# SPWM_PS_V1_00.net
KiCad netlist of a schematic drawn in Altium Designer
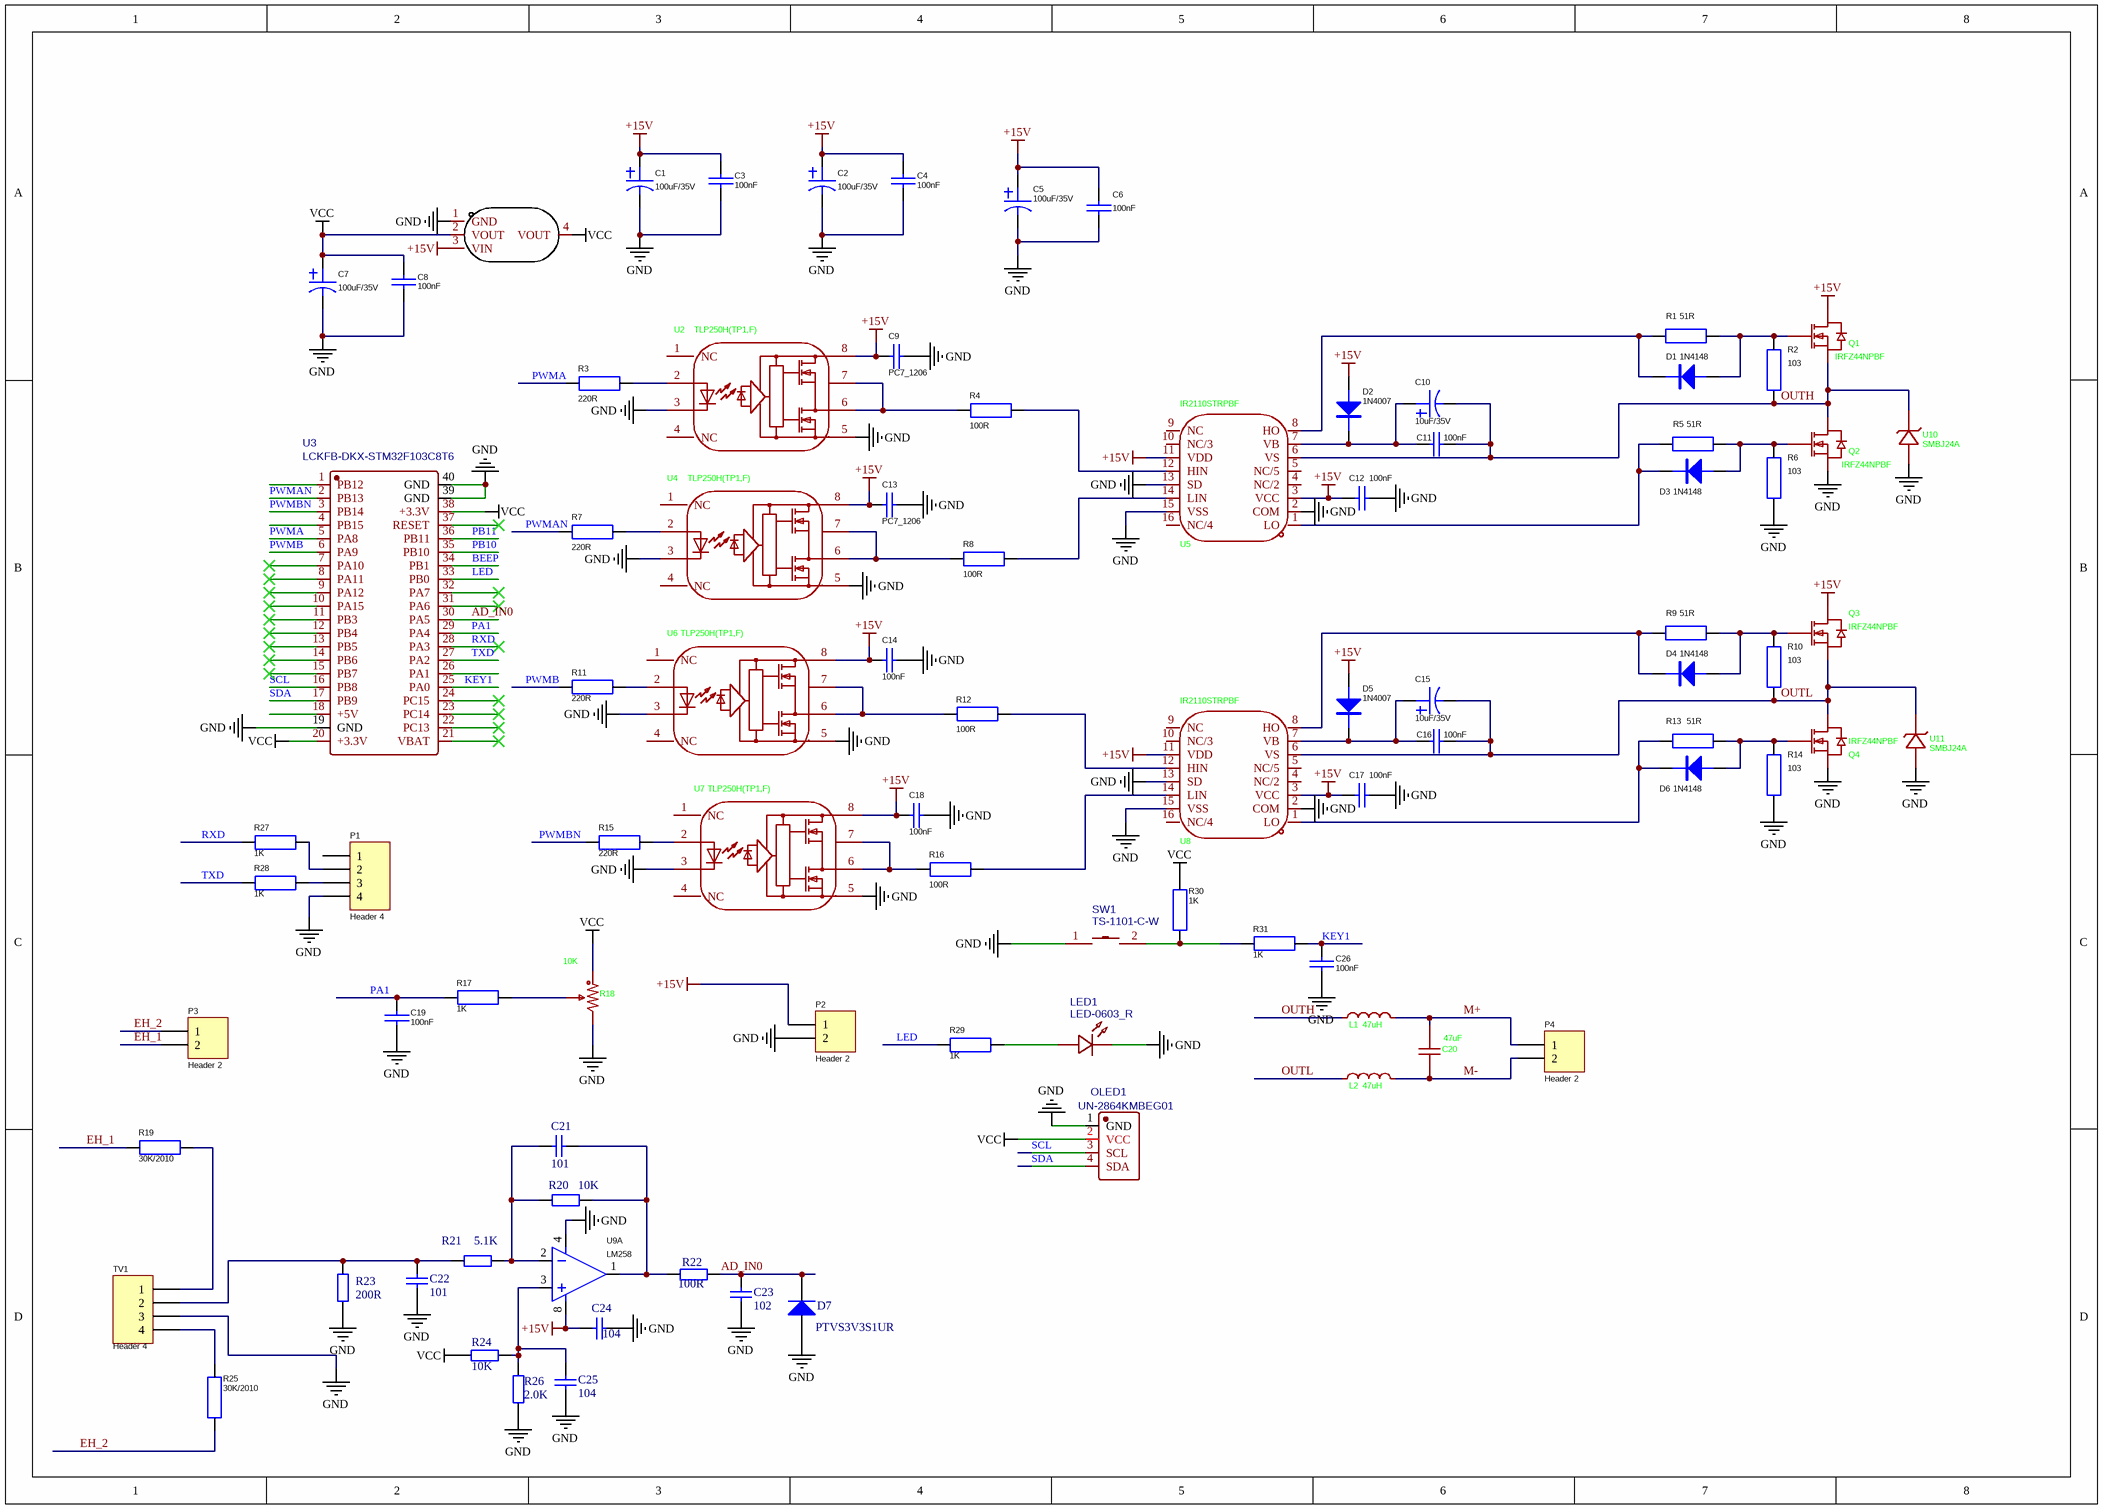
[diagram p0: SPWM_PS_V1.00.SCHDOC]

(export (version "E")
  (design (tool "Eeschema 10.0.6"))
  (components
    (comp (ref "C1")
      (value "100uF/35V")
      (footprint "PCD-10135-MB-36_100UF/35V")
      (description "PCD-10135-MB-36")
      (libsource (lib "Schlib") (part "PCD_100uF/35V"))
    )
    (comp (ref "C2")
      (value "100uF/35V")
      (footprint "PCD-10135-MB-36_100UF/35V")
      (description "PCD-10135-MB-36")
      (libsource (lib "Schlib") (part "PCD_100uF/35V"))
    )
    (comp (ref "C3")
      (value "100nF")
      (footprint "PC7-*****-KN-0A_0805")
      (description "PC7-*****-KM-0A_1206")
      (libsource (lib "Schlib") (part "PC7_1206"))
    )
    (comp (ref "C4")
      (value "100nF")
      (footprint "PC7-*****-KN-0A_0805")
      (description "PC7-*****-KM-0A_1206")
      (libsource (lib "Schlib") (part "PC7_1206"))
    )
    (comp (ref "C5")
      (value "100uF/35V")
      (footprint "PCD-10135-MB-36_100UF/35V")
      (description "PCD-10135-MB-36")
      (libsource (lib "Schlib") (part "PCD_100uF/35V"))
    )
    (comp (ref "C6")
      (value "100nF")
      (footprint "PC7-*****-KN-0A_0805")
      (description "PC7-*****-KM-0A_1206")
      (libsource (lib "Schlib") (part "PC7_1206"))
    )
    (comp (ref "C7")
      (value "100uF/35V")
      (footprint "PCD-10135-MB-36_100UF/35V")
      (description "PCD-10135-MB-36")
      (libsource (lib "Schlib") (part "PCD_100uF/35V"))
    )
    (comp (ref "C8")
      (value "100nF")
      (footprint "PC7-*****-KN-0A_0805")
      (description "PC7-*****-KM-0A_1206")
      (libsource (lib "Schlib") (part "PC7_1206"))
    )
    (comp (ref "C9")
      (value "PC7_1206")
      (footprint "PC7-*****-KN-0A_0805")
      (description "PC7-*****-KM-0A_1206")
      (libsource (lib "Schlib") (part "PC7_1206"))
    )
    (comp (ref "C10")
      (value "10uF/35V")
      (footprint "PCD-10050-MA-26_10UF/50V")
      (description "PCD-10135-MB-36")
      (libsource (lib "Schlib") (part "PCD_100uF/35V"))
    )
    (comp (ref "C11")
      (value "100nF")
      (footprint "PC7-*****-KN-0A_0805")
      (description "PC7-*****-KM-0A_1206")
      (libsource (lib "Schlib") (part "PC7_1206"))
    )
    (comp (ref "C12")
      (value "100nF")
      (footprint "PC7-*****-KN-0A_0805")
      (description "PC7-*****-KM-0A_1206")
      (libsource (lib "Schlib") (part "PC7_1206"))
    )
    (comp (ref "C13")
      (value "PC7_1206")
      (footprint "PC7-*****-KN-0A_0805")
      (description "PC7-*****-KM-0A_1206")
      (libsource (lib "Schlib") (part "PC7_1206"))
    )
    (comp (ref "C14")
      (value "100nF")
      (footprint "PC7-*****-KN-0A_0805")
      (description "PC7-*****-KM-0A_1206")
      (libsource (lib "Schlib") (part "PC7_1206"))
    )
    (comp (ref "C15")
      (value "10uF/35V")
      (footprint "PCD-10050-MA-26_10UF/50V")
      (description "PCD-10135-MB-36")
      (libsource (lib "Schlib") (part "PCD_100uF/35V"))
    )
    (comp (ref "C16")
      (value "100nF")
      (footprint "PC7-*****-KN-0A_0805")
      (description "PC7-*****-KM-0A_1206")
      (libsource (lib "Schlib") (part "PC7_1206"))
    )
    (comp (ref "C17")
      (value "100nF")
      (footprint "PC7-*****-KN-0A_0805")
      (description "PC7-*****-KM-0A_1206")
      (libsource (lib "Schlib") (part "PC7_1206"))
    )
    (comp (ref "C18")
      (value "100nF")
      (footprint "PC7-*****-KN-0A_0805")
      (description "PC7-*****-KM-0A_1206")
      (libsource (lib "Schlib") (part "PC7_1206"))
    )
    (comp (ref "C19")
      (value "100nF")
      (footprint "PC7-*****-KN-0A_0805")
      (description "PC7-*****-KM-0A_1206")
      (libsource (lib "Schlib") (part "PC7_1206"))
    )
    (comp (ref "C20")
      (value "47uF")
      (footprint "C2220")
      (fields (field (name "MANUFACTURER PART") "FS55X226K101LRG"))
      (libsource (lib "altium-import") (part "root_1_FS55X226K101LRG_"))
    )
    (comp (ref "C21")
      (value "101")
      (footprint "PC7-*****-KN-0A_0805")
      (description "Capacitor (Semiconductor SIM Model)")
      (fields (field (name "PUBLISHER") "Altium Limited"))
      (libsource (lib "Miscellaneous Devices") (part "Cap Semi"))
    )
    (comp (ref "C22")
      (value "101")
      (footprint "PC7-*****-KN-0A_0805")
      (description "Capacitor (Semiconductor SIM Model)")
      (fields (field (name "PUBLISHER") "Altium Limited"))
      (libsource (lib "Miscellaneous Devices") (part "Cap Semi"))
    )
    (comp (ref "C23")
      (value "102")
      (footprint "PC7-*****-KN-0A_0805")
      (description "Capacitor (Semiconductor SIM Model)")
      (fields (field (name "PUBLISHER") "Altium Limited"))
      (libsource (lib "Miscellaneous Devices") (part "Cap Semi"))
    )
    (comp (ref "C24")
      (value "104")
      (footprint "PC7-*****-KN-0A_0805")
      (description "Capacitor (Semiconductor SIM Model)")
      (fields (field (name "PUBLISHER") "Altium Limited"))
      (libsource (lib "Miscellaneous Devices") (part "Cap Semi"))
    )
    (comp (ref "C25")
      (value "104")
      (footprint "PC7-*****-KN-0A_0805")
      (description "Capacitor (Semiconductor SIM Model)")
      (fields (field (name "PUBLISHER") "Altium Limited"))
      (libsource (lib "Miscellaneous Devices") (part "Cap Semi"))
    )
    (comp (ref "C26")
      (value "100nF")
      (footprint "PC7-*****-KN-0A_0805")
      (description "PC7-*****-KM-0A_1206")
      (libsource (lib "Schlib") (part "PC7_1206"))
    )
    (comp (ref "D1")
      (value "1N4148")
      (footprint "PDD-00020-30-2A_RLS4148NTE-11-K")
      (description "PDD-00020-30-2A")
      (libsource (lib "Schlib") (part "PDD_RLS4148NTE-11-K"))
    )
    (comp (ref "D2")
      (value "1N4007")
      (footprint "PDD-00020-30-2A_RLS4148NTE-11-K")
      (description "PDD-00020-30-2A")
      (libsource (lib "Schlib") (part "PDD_RLS4148NTE-11-K"))
    )
    (comp (ref "D3")
      (value "1N4148")
      (footprint "PDD-00020-30-2A_RLS4148NTE-11-K")
      (description "PDD-00020-30-2A")
      (libsource (lib "Schlib") (part "PDD_RLS4148NTE-11-K"))
    )
    (comp (ref "D4")
      (value "1N4148")
      (footprint "PDD-00020-30-2A_RLS4148NTE-11-K")
      (description "PDD-00020-30-2A")
      (libsource (lib "Schlib") (part "PDD_RLS4148NTE-11-K"))
    )
    (comp (ref "D5")
      (value "1N4007")
      (footprint "PDD-00020-30-2A_RLS4148NTE-11-K")
      (description "PDD-00020-30-2A")
      (libsource (lib "Schlib") (part "PDD_RLS4148NTE-11-K"))
    )
    (comp (ref "D6")
      (value "1N4148")
      (footprint "PDD-00020-30-2A_RLS4148NTE-11-K")
      (description "PDD-00020-30-2A")
      (libsource (lib "Schlib") (part "PDD_RLS4148NTE-11-K"))
    )
    (comp (ref "D7")
      (value "PTVS3V3S1UR")
      (footprint "SOD123")
      (description "Default Diode")
      (fields (field (name "PUBLISHER") "Altium Limited"))
      (libsource (lib "Miscellaneous Devices") (part "Diode"))
    )
    (comp (ref "L1")
      (value "47uH")
      (footprint "IND-SMD_L13.8-W12.6_H6.5")
      (fields (field (name "MANUFACTURER PART") "YSPI1365-470M"))
      (libsource (lib "altium-import") (part "root_0_YSPI1365-470M_"))
    )
    (comp (ref "L2")
      (value "47uH")
      (footprint "IND-SMD_L13.8-W12.6_H6.5")
      (fields (field (name "MANUFACTURER PART") "YSPI1365-470M"))
      (libsource (lib "altium-import") (part "root_0_YSPI1365-470M_"))
    )
    (comp (ref "LED1")
      (value "LED-0603_R")
      (footprint "LED0603_RED")
      (fields
        (field (name "MANUFACTURER PART") "19-217/R6C-AL1M2VY/3T")
        (field (name "CONTRIBUTOR") "LCEDA_01")
      )
      (libsource (lib "altium-import") (part "root_0_LED-0603_R_"))
    )
    (comp (ref "OLED1")
      (value "UN-2864KMBEG01")
      (footprint "OLED-TH_4P-P2.54-L27.8-W27.3")
      (fields (field (name "CONTRIBUTOR") "lcsc"))
      (libsource (lib "altium-import") (part "root_0_UN-2864KMBEG01_"))
    )
    (comp (ref "P1")
      (value "Header 4")
      (footprint "HDR1X4")
      (description "Header, 4-Pin")
      (fields (field (name "PUBLISHER") "Altium Limited"))
      (libsource (lib "") (part "Header 4_1"))
    )
    (comp (ref "P2")
      (value "Header 2")
      (footprint "CONN-TH_2P-P5.00_WJ128V-5.0-2P")
      (description "Header, 2-Pin")
      (fields (field (name "PUBLISHER") "Altium Limited"))
      (libsource (lib "Miscellaneous Connectors") (part "Header 2"))
    )
    (comp (ref "P3")
      (value "Header 2")
      (footprint "CONN-TH_2P-P5.00_WJ128V-5.0-2P")
      (description "Header, 2-Pin")
      (fields (field (name "PUBLISHER") "Altium Limited"))
      (libsource (lib "Miscellaneous Connectors") (part "Header 2"))
    )
    (comp (ref "P4")
      (value "Header 2")
      (footprint "CONN-TH_2P-P5.00_WJ128V-5.0-2P")
      (description "Header, 2-Pin")
      (fields (field (name "PUBLISHER") "Altium Limited"))
      (libsource (lib "Miscellaneous Connectors") (part "Header 2"))
    )
    (comp (ref "Q1")
      (value "IRFZ44NPBF")
      (footprint "TO-220-3_L10.0-W4.5-P2.54-L")
      (libsource (lib "altium-import") (part "root_0_IRFZ44NPBF_"))
    )
    (comp (ref "Q2")
      (value "IRFZ44NPBF")
      (footprint "TO-220-3_L10.0-W4.5-P2.54-L")
      (libsource (lib "altium-import") (part "root_0_IRFZ44NPBF_"))
    )
    (comp (ref "Q3")
      (value "IRFZ44NPBF")
      (footprint "TO-220-3_L10.0-W4.5-P2.54-L")
      (libsource (lib "altium-import") (part "root_0_IRFZ44NPBF_"))
    )
    (comp (ref "Q4")
      (value "IRFZ44NPBF")
      (footprint "TO-220-3_L10.0-W4.5-P2.54-L")
      (libsource (lib "altium-import") (part "root_0_IRFZ44NPBF_"))
    )
    (comp (ref "R1")
      (value "51R")
      (footprint "PRC-*****-1M-0A_0805")
      (description "PRC-*****-2M-0A_1206")
      (libsource (lib "Schlib") (part "PRC_1206"))
    )
    (comp (ref "R2")
      (value "103")
      (footprint "PRC-*****-1M-0A_0805")
      (description "PRC-*****-2M-0A_1206")
      (libsource (lib "Schlib") (part "PRC_1206"))
    )
    (comp (ref "R3")
      (value "220R")
      (footprint "PRC-*****-1M-0A_0805")
      (description "PRC-*****-2M-0A_1206")
      (libsource (lib "Schlib") (part "PRC_1206"))
    )
    (comp (ref "R4")
      (value "100R")
      (footprint "PRC-*****-1M-0A_0805")
      (description "PRC-*****-2M-0A_1206")
      (libsource (lib "Schlib") (part "PRC_1206"))
    )
    (comp (ref "R5")
      (value "51R")
      (footprint "PRC-*****-1M-0A_0805")
      (description "PRC-*****-2M-0A_1206")
      (libsource (lib "Schlib") (part "PRC_1206"))
    )
    (comp (ref "R6")
      (value "103")
      (footprint "PRC-*****-1M-0A_0805")
      (description "PRC-*****-2M-0A_1206")
      (libsource (lib "Schlib") (part "PRC_1206"))
    )
    (comp (ref "R7")
      (value "220R")
      (footprint "PRC-*****-1M-0A_0805")
      (description "PRC-*****-2M-0A_1206")
      (libsource (lib "Schlib") (part "PRC_1206"))
    )
    (comp (ref "R8")
      (value "100R")
      (footprint "PRC-*****-1M-0A_0805")
      (description "PRC-*****-2M-0A_1206")
      (libsource (lib "Schlib") (part "PRC_1206"))
    )
    (comp (ref "R9")
      (value "51R")
      (footprint "PRC-*****-1M-0A_0805")
      (description "PRC-*****-2M-0A_1206")
      (libsource (lib "Schlib") (part "PRC_1206"))
    )
    (comp (ref "R10")
      (value "103")
      (footprint "PRC-*****-1M-0A_0805")
      (description "PRC-*****-2M-0A_1206")
      (libsource (lib "Schlib") (part "PRC_1206"))
    )
    (comp (ref "R11")
      (value "220R")
      (footprint "PRC-*****-1M-0A_0805")
      (description "PRC-*****-2M-0A_1206")
      (libsource (lib "Schlib") (part "PRC_1206"))
    )
    (comp (ref "R12")
      (value "100R")
      (footprint "PRC-*****-1M-0A_0805")
      (description "PRC-*****-2M-0A_1206")
      (libsource (lib "Schlib") (part "PRC_1206"))
    )
    (comp (ref "R13")
      (value "51R")
      (footprint "PRC-*****-1M-0A_0805")
      (description "PRC-*****-2M-0A_1206")
      (libsource (lib "Schlib") (part "PRC_1206"))
    )
    (comp (ref "R14")
      (value "103")
      (footprint "PRC-*****-1M-0A_0805")
      (description "PRC-*****-2M-0A_1206")
      (libsource (lib "Schlib") (part "PRC_1206"))
    )
    (comp (ref "R15")
      (value "220R")
      (footprint "PRC-*****-1M-0A_0805")
      (description "PRC-*****-2M-0A_1206")
      (libsource (lib "Schlib") (part "PRC_1206"))
    )
    (comp (ref "R16")
      (value "100R")
      (footprint "PRC-*****-1M-0A_0805")
      (description "PRC-*****-2M-0A_1206")
      (libsource (lib "Schlib") (part "PRC_1206"))
    )
    (comp (ref "R17")
      (value "1K")
      (footprint "PRC-*****-1M-0A_0805")
      (description "PRC-*****-2M-0A_1206")
      (libsource (lib "Schlib") (part "PRC_1206"))
    )
    (comp (ref "R18")
      (value "10K")
      (footprint "RES-ADJ-TH_RK09Y11L0001")
      (fields (field (name "MANUFACTURER PART") "RK09Y11L0001"))
      (libsource (lib "altium-import") (part "root_1_RK09Y11L0001_"))
    )
    (comp (ref "R19")
      (value "30K/2010")
      (footprint "PRC-*****-CM-0A_2010")
      (description "PRC-*****-CM-0A_2010")
      (libsource (lib "Schlib") (part "PRC_2010"))
    )
    (comp (ref "R20") (value "10K") (footprint "PRM-*****-1N-0A_0805") (libsource (lib "*") (part "RES-SM")))
    (comp (ref "R21") (value "5.1K") (footprint "PRM-*****-1N-0A_0805") (libsource (lib "*") (part "RES-SM")))
    (comp (ref "R22") (value "100R") (footprint "PRM-*****-1N-0A_0805") (libsource (lib "*") (part "RES-SM")))
    (comp (ref "R23")
      (value "200R")
      (footprint "PRM-*****-1N-0A_0805")
      (libsource (lib "") (part "RES-SM_3"))
    )
    (comp (ref "R24") (value "10K") (footprint "PRM-*****-1N-0A_0805") (libsource (lib "") (part "RES-SM_1")))
    (comp (ref "R25")
      (value "30K/2010")
      (footprint "PRC-*****-CM-0A_2010")
      (description "PRC-*****-CM-0A_2010")
      (libsource (lib "Schlib") (part "PRC_2010"))
    )
    (comp (ref "R26")
      (value "2.0K")
      (footprint "PRM-*****-1N-0A_0805")
      (libsource (lib "") (part "RES-SM_2"))
    )
    (comp (ref "R27")
      (value "1K")
      (footprint "PRC-*****-1M-0A_0805")
      (description "PRC-*****-2M-0A_1206")
      (libsource (lib "Schlib") (part "PRC_1206"))
    )
    (comp (ref "R28")
      (value "1K")
      (footprint "PRC-*****-1M-0A_0805")
      (description "PRC-*****-2M-0A_1206")
      (libsource (lib "Schlib") (part "PRC_1206"))
    )
    (comp (ref "R29")
      (value "1K")
      (footprint "PRC-*****-1M-0A_0805")
      (description "PRC-*****-2M-0A_1206")
      (libsource (lib "Schlib") (part "PRC_1206"))
    )
    (comp (ref "R30")
      (value "1K")
      (footprint "PRC-*****-1M-0A_0805")
      (description "PRC-*****-2M-0A_1206")
      (libsource (lib "Schlib") (part "PRC_1206"))
    )
    (comp (ref "R31")
      (value "1K")
      (footprint "PRC-*****-1M-0A_0805")
      (description "PRC-*****-2M-0A_1206")
      (libsource (lib "Schlib") (part "PRC_1206"))
    )
    (comp (ref "SW1")
      (value "TS-1101-C-W")
      (footprint "SW-SMD_L6.0-W3.3-LS8.0")
      (fields (field (name "CONTRIBUTOR") "LCSC"))
      (libsource (lib "altium-import") (part "root_0_TS-1101-C-W_"))
    )
    (comp (ref "TV1")
      (value "Header 4")
      (footprint "TV0815-1")
      (description "Header, 4-Pin")
      (fields (field (name "PUBLISHER") "Altium Limited"))
      (libsource (lib "Miscellaneous Connectors") (part "Header 4"))
    )
    (comp (ref "U1")
      (value "AMS1117-3.3")
      (footprint "SOT-223-3_L6.5-W3.4-P2.30-LS7.0-BR")
      (fields (field (name "MANUFACTURER") "AMS"))
      (libsource (lib "iomod_V1.00_20240818_1") (part "AMS1117-3.3_C6186"))
    )
    (comp (ref "U2")
      (value "TLP250H(TP1,F)")
      (footprint "SMD-8_L9.6-W6.4-P2.54-LS9.6-BL")
      (libsource (lib "altium-import") (part "root_0_TLP250H(TP1,F)_"))
    )
    (comp (ref "U3")
      (value "LCKFB-DKX-STM32F103C8T6")
      (footprint "CONN-TH_L53.3-W22.9_STM32F103C8T6-CARD")
      (fields (field (name "CONTRIBUTOR") "lcsc"))
      (libsource (lib "altium-import") (part "root_0_LCKFB-DKX-STM32F103C8T6_"))
    )
    (comp (ref "U4")
      (value "TLP250H(TP1,F)")
      (footprint "SMD-8_L9.6-W6.4-P2.54-LS9.6-BL")
      (libsource (lib "altium-import") (part "root_0_TLP250H(TP1,F)_"))
    )
    (comp (ref "U5")
      (value "IR2110STRPBF")
      (footprint "SOIC-16_L10.3-W7.5-P1.27-LS10.3-BL")
      (libsource (lib "altium-import") (part "root_2_IR2110STRPBF_"))
    )
    (comp (ref "U6")
      (value "TLP250H(TP1,F)")
      (footprint "SMD-8_L9.6-W6.4-P2.54-LS9.6-BL")
      (libsource (lib "altium-import") (part "root_0_TLP250H(TP1,F)_"))
    )
    (comp (ref "U7")
      (value "TLP250H(TP1,F)")
      (footprint "SMD-8_L9.6-W6.4-P2.54-LS9.6-BL")
      (libsource (lib "altium-import") (part "root_0_TLP250H(TP1,F)_"))
    )
    (comp (ref "U8")
      (value "IR2110STRPBF")
      (footprint "SOIC-16_L10.3-W7.5-P1.27-LS10.3-BL")
      (libsource (lib "altium-import") (part "root_2_IR2110STRPBF_"))
    )
    (comp (ref "U9")
      (value "LM258")
      (footprint "LM358-SOIC-8")
      (description "PIC-01330-01-20")
      (libsource (lib "Schlib") (part "PIC_NJM2904"))
    )
    (comp (ref "U10")
      (value "SMBJ24A")
      (footprint "SMB_L4.3-W3.6-LS5.3-RD")
      (libsource (lib "altium-import") (part "root_3_SMBJ24A_C19077578_"))
    )
    (comp (ref "U11")
      (value "SMBJ24A")
      (footprint "SMB_L4.3-W3.6-LS5.3-RD")
      (libsource (lib "altium-import") (part "root_3_SMBJ24A_C19077578_"))
    )
  )
  (nets
    (net (code "1") (name "+15V") (class "Default")
      (node (ref "C1") (pin "1") (pinfunction "1_1") (pintype "passive"))
      (node (ref "C12") (pin "1") (pinfunction "1_1") (pintype "passive"))
      (node (ref "C13") (pin "1") (pinfunction "1_1") (pintype "passive"))
      (node (ref "C14") (pin "1") (pinfunction "1_1") (pintype "passive"))
      (node (ref "C17") (pin "1") (pinfunction "1_1") (pintype "passive"))
      (node (ref "C18") (pin "1") (pinfunction "1_1") (pintype "passive"))
      (node (ref "C2") (pin "1") (pinfunction "1_1") (pintype "passive"))
      (node (ref "C24") (pin "1") (pinfunction "1_1") (pintype "passive"))
      (node (ref "C3") (pin "1") (pinfunction "1_1") (pintype "passive"))
      (node (ref "C4") (pin "1") (pinfunction "1_1") (pintype "passive"))
      (node (ref "C5") (pin "1") (pinfunction "1_1") (pintype "passive"))
      (node (ref "C6") (pin "1") (pinfunction "1_1") (pintype "passive"))
      (node (ref "C9") (pin "1") (pinfunction "1_1") (pintype "passive"))
      (node (ref "D2") (pin "2") (pinfunction "2_2") (pintype "passive"))
      (node (ref "D5") (pin "2") (pinfunction "2_2") (pintype "passive"))
      (node (ref "P2") (pin "1") (pinfunction "1_1") (pintype "passive"))
      (node (ref "Q1") (pin "2") (pinfunction "D_2") (pintype "passive"))
      (node (ref "Q3") (pin "2") (pinfunction "D_2") (pintype "passive"))
      (node (ref "U1") (pin "3") (pinfunction "VIN_3") (pintype "passive"))
      (node (ref "U2") (pin "8") (pinfunction "VCC_8") (pintype "passive"))
      (node (ref "U4") (pin "8") (pinfunction "VCC_8") (pintype "passive"))
      (node (ref "U5") (pin "11") (pinfunction "VDD_11") (pintype "passive"))
      (node (ref "U5") (pin "3") (pinfunction "VCC_3") (pintype "passive"))
      (node (ref "U6") (pin "8") (pinfunction "VCC_8") (pintype "passive"))
      (node (ref "U7") (pin "8") (pinfunction "VCC_8") (pintype "passive"))
      (node (ref "U8") (pin "11") (pinfunction "VDD_11") (pintype "passive"))
      (node (ref "U8") (pin "3") (pinfunction "VCC_3") (pintype "passive"))
      (node (ref "U9") (pin "8") (pintype "passive"))
    )
    (net (code "2") (name "/AD_IN0") (class "Default")
      (node (ref "C23") (pin "1") (pinfunction "1_1") (pintype "passive"))
      (node (ref "D7") (pin "2") (pinfunction "K_2") (pintype "passive"))
      (node (ref "R22") (pin "1") (pinfunction "1_1") (pintype "passive"))
      (node (ref "U3") (pin "30") (pinfunction "PA5_30") (pintype "passive"))
    )
    (net (code "3") (name "/BEEP") (class "Default")
      (node (ref "U3") (pin "34") (pinfunction "PB1_34") (pintype "passive"))
    )
    (net (code "4") (name "/EH_1") (class "Default")
      (node (ref "P3") (pin "2") (pinfunction "2_2") (pintype "passive"))
      (node (ref "R19") (pin "2") (pinfunction "2_2") (pintype "passive"))
    )
    (net (code "5") (name "/EH_2") (class "Default")
      (node (ref "P3") (pin "1") (pinfunction "1_1") (pintype "passive"))
      (node (ref "R25") (pin "1") (pinfunction "1_1") (pintype "passive"))
    )
    (net (code "6") (name "/KEY1") (class "Default")
      (node (ref "C26") (pin "2") (pinfunction "2_2") (pintype "passive"))
      (node (ref "R31") (pin "2") (pinfunction "2_2") (pintype "passive"))
      (node (ref "U3") (pin "25") (pinfunction "PA0_25") (pintype "passive"))
    )
    (net (code "7") (name "/LED") (class "Default")
      (node (ref "R29") (pin "1") (pinfunction "1_1") (pintype "passive"))
      (node (ref "U3") (pin "33") (pinfunction "PB0_33") (pintype "passive"))
    )
    (net (code "8") (name "/M+") (class "Default")
      (node (ref "C20") (pin "2") (pinfunction "2_2") (pintype "passive"))
      (node (ref "L1") (pin "2") (pinfunction "2_2") (pintype "passive"))
      (node (ref "P4") (pin "1") (pinfunction "1_1") (pintype "passive"))
    )
    (net (code "9") (name "/M-") (class "Default")
      (node (ref "C20") (pin "1") (pinfunction "1_1") (pintype "passive"))
      (node (ref "L2") (pin "2") (pinfunction "2_2") (pintype "passive"))
      (node (ref "P4") (pin "2") (pinfunction "2_2") (pintype "passive"))
    )
    (net (code "10") (name "/OUTH") (class "Default")
      (node (ref "C10") (pin "2") (pinfunction "2_2") (pintype "passive"))
      (node (ref "C11") (pin "2") (pinfunction "2_2") (pintype "passive"))
      (node (ref "L1") (pin "1") (pinfunction "1_1") (pintype "passive"))
      (node (ref "Q1") (pin "3") (pinfunction "S_3") (pintype "passive"))
      (node (ref "Q2") (pin "2") (pinfunction "D_2") (pintype "passive"))
      (node (ref "R2") (pin "1") (pinfunction "1_1") (pintype "passive"))
      (node (ref "U10") (pin "1") (pinfunction "C_1") (pintype "passive"))
      (node (ref "U5") (pin "6") (pinfunction "VS_6") (pintype "passive"))
    )
    (net (code "11") (name "/OUTL") (class "Default")
      (node (ref "C15") (pin "2") (pinfunction "2_2") (pintype "passive"))
      (node (ref "C16") (pin "2") (pinfunction "2_2") (pintype "passive"))
      (node (ref "L2") (pin "1") (pinfunction "1_1") (pintype "passive"))
      (node (ref "Q3") (pin "3") (pinfunction "S_3") (pintype "passive"))
      (node (ref "Q4") (pin "2") (pinfunction "D_2") (pintype "passive"))
      (node (ref "R10") (pin "1") (pinfunction "1_1") (pintype "passive"))
      (node (ref "U11") (pin "1") (pinfunction "C_1") (pintype "passive"))
      (node (ref "U8") (pin "6") (pinfunction "VS_6") (pintype "passive"))
    )
    (net (code "12") (name "/PA1") (class "Default")
      (node (ref "C19") (pin "2") (pinfunction "2_2") (pintype "passive"))
      (node (ref "R17") (pin "1") (pinfunction "1_1") (pintype "passive"))
      (node (ref "U3") (pin "29") (pinfunction "PA4_29") (pintype "passive"))
    )
    (net (code "13") (name "/PB10") (class "Default")
      (node (ref "U3") (pin "35") (pinfunction "PB10_35") (pintype "passive"))
    )
    (net (code "14") (name "/PB11") (class "Default")
      (node (ref "U3") (pin "36") (pinfunction "PB11_36") (pintype "passive"))
    )
    (net (code "15") (name "/PWMA") (class "Default")
      (node (ref "R3") (pin "1") (pinfunction "1_1") (pintype "passive"))
      (node (ref "U3") (pin "5") (pinfunction "PA8_5") (pintype "passive"))
    )
    (net (code "16") (name "/PWMAN") (class "Default")
      (node (ref "R7") (pin "1") (pinfunction "1_1") (pintype "passive"))
      (node (ref "U3") (pin "2") (pinfunction "PB13_2") (pintype "passive"))
    )
    (net (code "17") (name "/PWMB") (class "Default")
      (node (ref "R11") (pin "1") (pinfunction "1_1") (pintype "passive"))
      (node (ref "U3") (pin "6") (pinfunction "PA9_6") (pintype "passive"))
    )
    (net (code "18") (name "/PWMBN") (class "Default")
      (node (ref "R15") (pin "1") (pinfunction "1_1") (pintype "passive"))
      (node (ref "U3") (pin "3") (pinfunction "PB14_3") (pintype "passive"))
    )
    (net (code "19") (name "/RXD") (class "Default")
      (node (ref "R27") (pin "1") (pinfunction "1_1") (pintype "passive"))
      (node (ref "U3") (pin "28") (pinfunction "PA3_28") (pintype "passive"))
    )
    (net (code "20") (name "/SCL") (class "Default")
      (node (ref "OLED1") (pin "3") (pinfunction "SCL_3") (pintype "passive"))
      (node (ref "U3") (pin "16") (pinfunction "PB8_16") (pintype "passive"))
    )
    (net (code "21") (name "/SDA") (class "Default")
      (node (ref "OLED1") (pin "4") (pinfunction "SDA_4") (pintype "passive"))
      (node (ref "U3") (pin "17") (pinfunction "PB9_17") (pintype "passive"))
    )
    (net (code "22") (name "/TXD") (class "Default")
      (node (ref "R28") (pin "1") (pinfunction "1_1") (pintype "passive"))
      (node (ref "U3") (pin "27") (pinfunction "PA2_27") (pintype "passive"))
    )
    (net (code "23") (name "GND") (class "Default")
      (node (ref "C1") (pin "2") (pinfunction "2_2") (pintype "passive"))
      (node (ref "C12") (pin "2") (pinfunction "2_2") (pintype "passive"))
      (node (ref "C13") (pin "2") (pinfunction "2_2") (pintype "passive"))
      (node (ref "C14") (pin "2") (pinfunction "2_2") (pintype "passive"))
      (node (ref "C17") (pin "2") (pinfunction "2_2") (pintype "passive"))
      (node (ref "C18") (pin "2") (pinfunction "2_2") (pintype "passive"))
      (node (ref "C19") (pin "1") (pinfunction "1_1") (pintype "passive"))
      (node (ref "C2") (pin "2") (pinfunction "2_2") (pintype "passive"))
      (node (ref "C22") (pin "1") (pinfunction "1_1") (pintype "passive"))
      (node (ref "C23") (pin "2") (pinfunction "2_2") (pintype "passive"))
      (node (ref "C24") (pin "2") (pinfunction "2_2") (pintype "passive"))
      (node (ref "C25") (pin "1") (pinfunction "1_1") (pintype "passive"))
      (node (ref "C26") (pin "1") (pinfunction "1_1") (pintype "passive"))
      (node (ref "C3") (pin "2") (pinfunction "2_2") (pintype "passive"))
      (node (ref "C4") (pin "2") (pinfunction "2_2") (pintype "passive"))
      (node (ref "C5") (pin "2") (pinfunction "2_2") (pintype "passive"))
      (node (ref "C6") (pin "2") (pinfunction "2_2") (pintype "passive"))
      (node (ref "C7") (pin "2") (pinfunction "2_2") (pintype "passive"))
      (node (ref "C8") (pin "2") (pinfunction "2_2") (pintype "passive"))
      (node (ref "C9") (pin "2") (pinfunction "2_2") (pintype "passive"))
      (node (ref "D7") (pin "1") (pinfunction "A_1") (pintype "passive"))
      (node (ref "LED1") (pin "2") (pinfunction "2_2") (pintype "passive"))
      (node (ref "OLED1") (pin "1") (pinfunction "GND_1") (pintype "passive"))
      (node (ref "P1") (pin "4") (pinfunction "4_4") (pintype "passive"))
      (node (ref "P2") (pin "2") (pinfunction "2_2") (pintype "passive"))
      (node (ref "Q2") (pin "3") (pinfunction "S_3") (pintype "passive"))
      (node (ref "Q4") (pin "3") (pinfunction "S_3") (pintype "passive"))
      (node (ref "R14") (pin "1") (pinfunction "1_1") (pintype "passive"))
      (node (ref "R18") (pin "3") (pinfunction "3_3") (pintype "passive"))
      (node (ref "R23") (pin "1") (pinfunction "1_1") (pintype "passive"))
      (node (ref "R26") (pin "2") (pinfunction "2_2") (pintype "passive"))
      (node (ref "R6") (pin "1") (pinfunction "1_1") (pintype "passive"))
      (node (ref "SW1") (pin "1") (pinfunction "1_1") (pintype "passive"))
      (node (ref "TV1") (pin "3") (pinfunction "3_3") (pintype "passive"))
      (node (ref "U1") (pin "1") (pinfunction "GND_1") (pintype "passive"))
      (node (ref "U10") (pin "2") (pinfunction "A_2") (pintype "passive"))
      (node (ref "U11") (pin "2") (pinfunction "A_2") (pintype "passive"))
      (node (ref "U2") (pin "3") (pinfunction "CAT_3") (pintype "passive"))
      (node (ref "U2") (pin "5") (pinfunction "GND_5") (pintype "passive"))
      (node (ref "U3") (pin "19") (pinfunction "GND_19") (pintype "passive"))
      (node (ref "U3") (pin "39") (pinfunction "GND_39") (pintype "passive"))
      (node (ref "U3") (pin "40") (pinfunction "GND_40") (pintype "passive"))
      (node (ref "U4") (pin "3") (pinfunction "CAT_3") (pintype "passive"))
      (node (ref "U4") (pin "5") (pinfunction "GND_5") (pintype "passive"))
      (node (ref "U5") (pin "13") (pinfunction "SD_13") (pintype "passive"))
      (node (ref "U5") (pin "15") (pinfunction "VSS_15") (pintype "passive"))
      (node (ref "U5") (pin "2") (pinfunction "COM_2") (pintype "passive"))
      (node (ref "U6") (pin "3") (pinfunction "CAT_3") (pintype "passive"))
      (node (ref "U6") (pin "5") (pinfunction "GND_5") (pintype "passive"))
      (node (ref "U7") (pin "3") (pinfunction "CAT_3") (pintype "passive"))
      (node (ref "U7") (pin "5") (pinfunction "GND_5") (pintype "passive"))
      (node (ref "U8") (pin "13") (pinfunction "SD_13") (pintype "passive"))
      (node (ref "U8") (pin "15") (pinfunction "VSS_15") (pintype "passive"))
      (node (ref "U8") (pin "2") (pinfunction "COM_2") (pintype "passive"))
      (node (ref "U9") (pin "4") (pintype "passive"))
    )
    (net (code "24") (name "Net-(C21-Pad1)") (class "Default")
      (node (ref "C21") (pin "1") (pinfunction "1_1") (pintype "passive"))
      (node (ref "R20") (pin "1") (pinfunction "1_1") (pintype "passive"))
      (node (ref "R22") (pin "2") (pinfunction "2_2") (pintype "passive"))
      (node (ref "U9") (pin "1") (pintype "passive"))
    )
    (net (code "25") (name "Net-(C21-Pad2)") (class "Default")
      (node (ref "C21") (pin "2") (pinfunction "2_2") (pintype "passive"))
      (node (ref "R20") (pin "2") (pinfunction "2_2") (pintype "passive"))
      (node (ref "R21") (pin "1") (pinfunction "1_1") (pintype "passive"))
      (node (ref "U9") (pin "2") (pintype "passive"))
    )
    (net (code "26") (name "Net-(C22-Pad2)") (class "Default")
      (node (ref "C22") (pin "2") (pinfunction "2_2") (pintype "passive"))
      (node (ref "R21") (pin "2") (pinfunction "2_2") (pintype "passive"))
      (node (ref "R23") (pin "2") (pinfunction "2_2") (pintype "passive"))
      (node (ref "TV1") (pin "2") (pinfunction "2_2") (pintype "passive"))
    )
    (net (code "27") (name "Net-(C25-Pad2)") (class "Default")
      (node (ref "C25") (pin "2") (pinfunction "2_2") (pintype "passive"))
      (node (ref "R24") (pin "2") (pinfunction "2_2") (pintype "passive"))
      (node (ref "R26") (pin "1") (pinfunction "1_1") (pintype "passive"))
      (node (ref "U9") (pin "3") (pintype "passive"))
    )
    (net (code "28") (name "Net-(D1-Pad1)") (class "Default")
      (node (ref "D1") (pin "1") (pinfunction "1_1") (pintype "passive"))
    )
    (net (code "29") (name "Net-(D1-Pad2)") (class "Default")
      (node (ref "D1") (pin "2") (pinfunction "2_2") (pintype "passive"))
    )
    (net (code "30") (name "Net-(D2-Pad1)") (class "Default")
      (node (ref "D2") (pin "1") (pinfunction "1_1") (pintype "passive"))
    )
    (net (code "31") (name "Net-(D2-Pad2)") (class "Default")
      (node (ref "D2") (pin "2") (pinfunction "2_2") (pintype "passive"))
    )
    (net (code "32") (name "Net-(D3-Pad1)") (class "Default")
      (node (ref "D3") (pin "1") (pinfunction "1_1") (pintype "passive"))
    )
    (net (code "33") (name "Net-(D3-Pad2)") (class "Default")
      (node (ref "D3") (pin "2") (pinfunction "2_2") (pintype "passive"))
    )
    (net (code "34") (name "Net-(D4-Pad1)") (class "Default")
      (node (ref "D4") (pin "1") (pinfunction "1_1") (pintype "passive"))
    )
    (net (code "35") (name "Net-(D4-Pad2)") (class "Default")
      (node (ref "D4") (pin "2") (pinfunction "2_2") (pintype "passive"))
    )
    (net (code "36") (name "Net-(D5-Pad1)") (class "Default")
      (node (ref "D5") (pin "1") (pinfunction "1_1") (pintype "passive"))
    )
    (net (code "37") (name "Net-(D5-Pad2)") (class "Default")
      (node (ref "D5") (pin "2") (pinfunction "2_2") (pintype "passive"))
    )
    (net (code "38") (name "Net-(D6-Pad1)") (class "Default")
      (node (ref "D6") (pin "1") (pinfunction "1_1") (pintype "passive"))
    )
    (net (code "39") (name "Net-(D6-Pad2)") (class "Default")
      (node (ref "D6") (pin "2") (pinfunction "2_2") (pintype "passive"))
    )
    (net (code "40") (name "Net-(LED1-Pad1)") (class "Default")
      (node (ref "LED1") (pin "1") (pinfunction "1_1") (pintype "passive"))
      (node (ref "R29") (pin "2") (pinfunction "2_2") (pintype "passive"))
    )
    (net (code "41") (name "Net-(P1-Pad2)") (class "Default")
      (node (ref "P1") (pin "2") (pinfunction "2_2") (pintype "passive"))
      (node (ref "R27") (pin "2") (pinfunction "2_2") (pintype "passive"))
    )
    (net (code "42") (name "Net-(P1-Pad3)") (class "Default")
      (node (ref "P1") (pin "3") (pinfunction "3_3") (pintype "passive"))
      (node (ref "R28") (pin "2") (pinfunction "2_2") (pintype "passive"))
    )
    (net (code "43") (name "Net-(Q1-G)") (class "Default")
      (node (ref "D1") (pin "2") (pinfunction "2_2") (pintype "passive"))
      (node (ref "Q1") (pin "1") (pinfunction "G_1") (pintype "passive"))
      (node (ref "R1") (pin "2") (pinfunction "2_2") (pintype "passive"))
      (node (ref "R2") (pin "2") (pinfunction "2_2") (pintype "passive"))
    )
    (net (code "44") (name "Net-(Q2-G)") (class "Default")
      (node (ref "D3") (pin "2") (pinfunction "2_2") (pintype "passive"))
      (node (ref "Q2") (pin "1") (pinfunction "G_1") (pintype "passive"))
      (node (ref "R5") (pin "2") (pinfunction "2_2") (pintype "passive"))
      (node (ref "R6") (pin "2") (pinfunction "2_2") (pintype "passive"))
    )
    (net (code "45") (name "Net-(Q3-G)") (class "Default")
      (node (ref "D4") (pin "2") (pinfunction "2_2") (pintype "passive"))
      (node (ref "Q3") (pin "1") (pinfunction "G_1") (pintype "passive"))
      (node (ref "R10") (pin "2") (pinfunction "2_2") (pintype "passive"))
      (node (ref "R9") (pin "2") (pinfunction "2_2") (pintype "passive"))
    )
    (net (code "46") (name "Net-(Q4-G)") (class "Default")
      (node (ref "D6") (pin "2") (pinfunction "2_2") (pintype "passive"))
      (node (ref "Q4") (pin "1") (pinfunction "G_1") (pintype "passive"))
      (node (ref "R13") (pin "2") (pinfunction "2_2") (pintype "passive"))
      (node (ref "R14") (pin "2") (pinfunction "2_2") (pintype "passive"))
    )
    (net (code "47") (name "Net-(R17-Pad2)") (class "Default")
      (node (ref "R17") (pin "2") (pinfunction "2_2") (pintype "passive"))
      (node (ref "R18") (pin "2") (pinfunction "2_2") (pintype "passive"))
    )
    (net (code "48") (name "Net-(R19-Pad1)") (class "Default")
      (node (ref "R19") (pin "1") (pinfunction "1_1") (pintype "passive"))
      (node (ref "TV1") (pin "1") (pinfunction "1_1") (pintype "passive"))
    )
    (net (code "49") (name "Net-(R25-Pad2)") (class "Default")
      (node (ref "R25") (pin "2") (pinfunction "2_2") (pintype "passive"))
      (node (ref "TV1") (pin "4") (pinfunction "4_4") (pintype "passive"))
    )
    (net (code "50") (name "Net-(R30-Pad1)") (class "Default")
      (node (ref "R30") (pin "1") (pinfunction "1_1") (pintype "passive"))
      (node (ref "R31") (pin "1") (pinfunction "1_1") (pintype "passive"))
      (node (ref "SW1") (pin "2") (pinfunction "2_2") (pintype "passive"))
    )
    (net (code "51") (name "Net-(U2-AN)") (class "Default")
      (node (ref "R3") (pin "2") (pinfunction "2_2") (pintype "passive"))
      (node (ref "U2") (pin "2") (pinfunction "AN_2") (pintype "passive"))
    )
    (net (code "52") (name "Net-(U2-VO)") (class "Default")
      (node (ref "R4") (pin "1") (pinfunction "1_1") (pintype "passive"))
      (node (ref "U2") (pin "6") (pinfunction "VO_6") (pintype "passive"))
      (node (ref "U2") (pin "7") (pinfunction "NC_7") (pintype "passive"))
    )
    (net (code "53") (name "Net-(U4-AN)") (class "Default")
      (node (ref "R7") (pin "2") (pinfunction "2_2") (pintype "passive"))
      (node (ref "U4") (pin "2") (pinfunction "AN_2") (pintype "passive"))
    )
    (net (code "54") (name "Net-(U4-VO)") (class "Default")
      (node (ref "R8") (pin "1") (pinfunction "1_1") (pintype "passive"))
      (node (ref "U4") (pin "6") (pinfunction "VO_6") (pintype "passive"))
      (node (ref "U4") (pin "7") (pinfunction "NC_7") (pintype "passive"))
    )
    (net (code "55") (name "Net-(U5-HIN)") (class "Default")
      (node (ref "R4") (pin "2") (pinfunction "2_2") (pintype "passive"))
      (node (ref "U5") (pin "12") (pinfunction "HIN_12") (pintype "passive"))
    )
    (net (code "56") (name "Net-(U5-HO)") (class "Default")
      (node (ref "D1") (pin "1") (pinfunction "1_1") (pintype "passive"))
      (node (ref "R1") (pin "1") (pinfunction "1_1") (pintype "passive"))
      (node (ref "U5") (pin "8") (pinfunction "HO_8") (pintype "passive"))
    )
    (net (code "57") (name "Net-(U5-LIN)") (class "Default")
      (node (ref "R8") (pin "2") (pinfunction "2_2") (pintype "passive"))
      (node (ref "U5") (pin "14") (pinfunction "LIN_14") (pintype "passive"))
    )
    (net (code "58") (name "Net-(U5-LO)") (class "Default")
      (node (ref "D3") (pin "1") (pinfunction "1_1") (pintype "passive"))
      (node (ref "R5") (pin "1") (pinfunction "1_1") (pintype "passive"))
      (node (ref "U5") (pin "1") (pinfunction "LO_1") (pintype "passive"))
    )
    (net (code "59") (name "Net-(U5-VB)") (class "Default")
      (node (ref "C10") (pin "1") (pinfunction "1_1") (pintype "passive"))
      (node (ref "C11") (pin "1") (pinfunction "1_1") (pintype "passive"))
      (node (ref "D2") (pin "1") (pinfunction "1_1") (pintype "passive"))
      (node (ref "U5") (pin "7") (pinfunction "VB_7") (pintype "passive"))
    )
    (net (code "60") (name "Net-(U6-AN)") (class "Default")
      (node (ref "R11") (pin "2") (pinfunction "2_2") (pintype "passive"))
      (node (ref "U6") (pin "2") (pinfunction "AN_2") (pintype "passive"))
    )
    (net (code "61") (name "Net-(U6-VO)") (class "Default")
      (node (ref "R12") (pin "1") (pinfunction "1_1") (pintype "passive"))
      (node (ref "U6") (pin "6") (pinfunction "VO_6") (pintype "passive"))
      (node (ref "U6") (pin "7") (pinfunction "NC_7") (pintype "passive"))
    )
    (net (code "62") (name "Net-(U7-AN)") (class "Default")
      (node (ref "R15") (pin "2") (pinfunction "2_2") (pintype "passive"))
      (node (ref "U7") (pin "2") (pinfunction "AN_2") (pintype "passive"))
    )
    (net (code "63") (name "Net-(U7-VO)") (class "Default")
      (node (ref "R16") (pin "1") (pinfunction "1_1") (pintype "passive"))
      (node (ref "U7") (pin "6") (pinfunction "VO_6") (pintype "passive"))
      (node (ref "U7") (pin "7") (pinfunction "NC_7") (pintype "passive"))
    )
    (net (code "64") (name "Net-(U8-HIN)") (class "Default")
      (node (ref "R12") (pin "2") (pinfunction "2_2") (pintype "passive"))
      (node (ref "U8") (pin "12") (pinfunction "HIN_12") (pintype "passive"))
    )
    (net (code "65") (name "Net-(U8-HO)") (class "Default")
      (node (ref "D4") (pin "1") (pinfunction "1_1") (pintype "passive"))
      (node (ref "R9") (pin "1") (pinfunction "1_1") (pintype "passive"))
      (node (ref "U8") (pin "8") (pinfunction "HO_8") (pintype "passive"))
    )
    (net (code "66") (name "Net-(U8-LIN)") (class "Default")
      (node (ref "R16") (pin "2") (pinfunction "2_2") (pintype "passive"))
      (node (ref "U8") (pin "14") (pinfunction "LIN_14") (pintype "passive"))
    )
    (net (code "67") (name "Net-(U8-LO)") (class "Default")
      (node (ref "D6") (pin "1") (pinfunction "1_1") (pintype "passive"))
      (node (ref "R13") (pin "1") (pinfunction "1_1") (pintype "passive"))
      (node (ref "U8") (pin "1") (pinfunction "LO_1") (pintype "passive"))
    )
    (net (code "68") (name "Net-(U8-VB)") (class "Default")
      (node (ref "C15") (pin "1") (pinfunction "1_1") (pintype "passive"))
      (node (ref "C16") (pin "1") (pinfunction "1_1") (pintype "passive"))
      (node (ref "D5") (pin "1") (pinfunction "1_1") (pintype "passive"))
      (node (ref "U8") (pin "7") (pinfunction "VB_7") (pintype "passive"))
    )
    (net (code "69") (name "VCC") (class "Default")
      (node (ref "C7") (pin "1") (pinfunction "1_1") (pintype "passive"))
      (node (ref "C8") (pin "1") (pinfunction "1_1") (pintype "passive"))
      (node (ref "OLED1") (pin "2") (pinfunction "VCC_2") (pintype "passive"))
      (node (ref "R18") (pin "1") (pinfunction "1_1") (pintype "passive"))
      (node (ref "R24") (pin "1") (pinfunction "1_1") (pintype "passive"))
      (node (ref "R30") (pin "2") (pinfunction "2_2") (pintype "passive"))
      (node (ref "U1") (pin "2") (pinfunction "VOUT_2") (pintype "passive"))
      (node (ref "U1") (pin "4") (pinfunction "VOUT_4") (pintype "passive"))
      (node (ref "U3") (pin "20") (pinfunction "+3.3V_20") (pintype "passive"))
      (node (ref "U3") (pin "38") (pinfunction "+3.3V_38") (pintype "passive"))
    )
    (net (code "70") (name "unconnected-(P1-Pad1)") (class "Default")
      (node (ref "P1") (pin "1") (pinfunction "1_1") (pintype "passive"))
    )
    (net (code "71") (name "unconnected-(U2-NC-Pad1)") (class "Default")
      (node (ref "U2") (pin "1") (pinfunction "NC_1") (pintype "passive"))
    )
    (net (code "72") (name "unconnected-(U2-NC-Pad4)") (class "Default")
      (node (ref "U2") (pin "4") (pinfunction "NC_4") (pintype "passive"))
    )
    (net (code "73") (name "unconnected-(U3-+5V-Pad18)") (class "Default")
      (node (ref "U3") (pin "18") (pinfunction "+5V_18") (pintype "passive"))
    )
    (net (code "74") (name "unconnected-(U3-PA1-Pad26)") (class "Default")
      (node (ref "U3") (pin "26") (pinfunction "PA1_26") (pintype "passive"))
    )
    (net (code "75") (name "unconnected-(U3-PA6-Pad31)") (class "Default")
      (node (ref "U3") (pin "31") (pinfunction "PA6_31") (pintype "passive+no_connect"))
    )
    (net (code "76") (name "unconnected-(U3-PA7-Pad32)") (class "Default")
      (node (ref "U3") (pin "32") (pinfunction "PA7_32") (pintype "passive+no_connect"))
    )
    (net (code "77") (name "unconnected-(U3-PA10-Pad7)") (class "Default")
      (node (ref "U3") (pin "7") (pinfunction "PA10_7") (pintype "passive+no_connect"))
    )
    (net (code "78") (name "unconnected-(U3-PA11-Pad8)") (class "Default")
      (node (ref "U3") (pin "8") (pinfunction "PA11_8") (pintype "passive+no_connect"))
    )
    (net (code "79") (name "unconnected-(U3-PA12-Pad9)") (class "Default")
      (node (ref "U3") (pin "9") (pinfunction "PA12_9") (pintype "passive+no_connect"))
    )
    (net (code "80") (name "unconnected-(U3-PA15-Pad10)") (class "Default")
      (node (ref "U3") (pin "10") (pinfunction "PA15_10") (pintype "passive+no_connect"))
    )
    (net (code "81") (name "unconnected-(U3-PB3-Pad11)") (class "Default")
      (node (ref "U3") (pin "11") (pinfunction "PB3_11") (pintype "passive+no_connect"))
    )
    (net (code "82") (name "unconnected-(U3-PB4-Pad12)") (class "Default")
      (node (ref "U3") (pin "12") (pinfunction "PB4_12") (pintype "passive+no_connect"))
    )
    (net (code "83") (name "unconnected-(U3-PB5-Pad13)") (class "Default")
      (node (ref "U3") (pin "13") (pinfunction "PB5_13") (pintype "passive+no_connect"))
    )
    (net (code "84") (name "unconnected-(U3-PB6-Pad14)") (class "Default")
      (node (ref "U3") (pin "14") (pinfunction "PB6_14") (pintype "passive+no_connect"))
    )
    (net (code "85") (name "unconnected-(U3-PB7-Pad15)") (class "Default")
      (node (ref "U3") (pin "15") (pinfunction "PB7_15") (pintype "passive+no_connect"))
    )
    (net (code "86") (name "unconnected-(U3-PB12-Pad1)") (class "Default")
      (node (ref "U3") (pin "1") (pinfunction "PB12_1") (pintype "passive"))
    )
    (net (code "87") (name "unconnected-(U3-PB15-Pad4)") (class "Default")
      (node (ref "U3") (pin "4") (pinfunction "PB15_4") (pintype "passive"))
    )
    (net (code "88") (name "unconnected-(U3-PC13-Pad22)") (class "Default")
      (node (ref "U3") (pin "22") (pinfunction "PC13_22") (pintype "passive+no_connect"))
    )
    (net (code "89") (name "unconnected-(U3-PC14-Pad23)") (class "Default")
      (node (ref "U3") (pin "23") (pinfunction "PC14_23") (pintype "passive+no_connect"))
    )
    (net (code "90") (name "unconnected-(U3-PC15-Pad24)") (class "Default")
      (node (ref "U3") (pin "24") (pinfunction "PC15_24") (pintype "passive+no_connect"))
    )
    (net (code "91") (name "unconnected-(U3-RESET-Pad37)") (class "Default")
      (node (ref "U3") (pin "37") (pinfunction "RESET_37") (pintype "passive+no_connect"))
    )
    (net (code "92") (name "unconnected-(U3-VBAT-Pad21)") (class "Default")
      (node (ref "U3") (pin "21") (pinfunction "VBAT_21") (pintype "passive+no_connect"))
    )
    (net (code "93") (name "unconnected-(U4-NC-Pad1)") (class "Default")
      (node (ref "U4") (pin "1") (pinfunction "NC_1") (pintype "passive"))
    )
    (net (code "94") (name "unconnected-(U4-NC-Pad4)") (class "Default")
      (node (ref "U4") (pin "4") (pinfunction "NC_4") (pintype "passive"))
    )
    (net (code "95") (name "unconnected-(U5-NC-Pad9)") (class "Default")
      (node (ref "U5") (pin "9") (pinfunction "NC_9") (pintype "passive"))
    )
    (net (code "96") (name "unconnected-(U5-NC{slash}2-Pad4)") (class "Default")
      (node (ref "U5") (pin "4") (pinfunction "NC/2_4") (pintype "passive"))
    )
    (net (code "97") (name "unconnected-(U5-NC{slash}3-Pad10)") (class "Default")
      (node (ref "U5") (pin "10") (pinfunction "NC/3_10") (pintype "passive"))
    )
    (net (code "98") (name "unconnected-(U5-NC{slash}4-Pad16)") (class "Default")
      (node (ref "U5") (pin "16") (pinfunction "NC/4_16") (pintype "passive"))
    )
    (net (code "99") (name "unconnected-(U5-NC{slash}5-Pad5)") (class "Default")
      (node (ref "U5") (pin "5") (pinfunction "NC/5_5") (pintype "passive"))
    )
    (net (code "100") (name "unconnected-(U6-NC-Pad1)") (class "Default")
      (node (ref "U6") (pin "1") (pinfunction "NC_1") (pintype "passive"))
    )
    (net (code "101") (name "unconnected-(U6-NC-Pad4)") (class "Default")
      (node (ref "U6") (pin "4") (pinfunction "NC_4") (pintype "passive"))
    )
    (net (code "102") (name "unconnected-(U7-NC-Pad1)") (class "Default")
      (node (ref "U7") (pin "1") (pinfunction "NC_1") (pintype "passive"))
    )
    (net (code "103") (name "unconnected-(U7-NC-Pad4)") (class "Default")
      (node (ref "U7") (pin "4") (pinfunction "NC_4") (pintype "passive"))
    )
    (net (code "104") (name "unconnected-(U8-NC-Pad9)") (class "Default")
      (node (ref "U8") (pin "9") (pinfunction "NC_9") (pintype "passive"))
    )
    (net (code "105") (name "unconnected-(U8-NC{slash}2-Pad4)") (class "Default")
      (node (ref "U8") (pin "4") (pinfunction "NC/2_4") (pintype "passive"))
    )
    (net (code "106") (name "unconnected-(U8-NC{slash}3-Pad10)") (class "Default")
      (node (ref "U8") (pin "10") (pinfunction "NC/3_10") (pintype "passive"))
    )
    (net (code "107") (name "unconnected-(U8-NC{slash}4-Pad16)") (class "Default")
      (node (ref "U8") (pin "16") (pinfunction "NC/4_16") (pintype "passive"))
    )
    (net (code "108") (name "unconnected-(U8-NC{slash}5-Pad5)") (class "Default")
      (node (ref "U8") (pin "5") (pinfunction "NC/5_5") (pintype "passive"))
    )
  )
)
